# Sheet1.net
KiCad netlist of a schematic drawn in Altium Designer
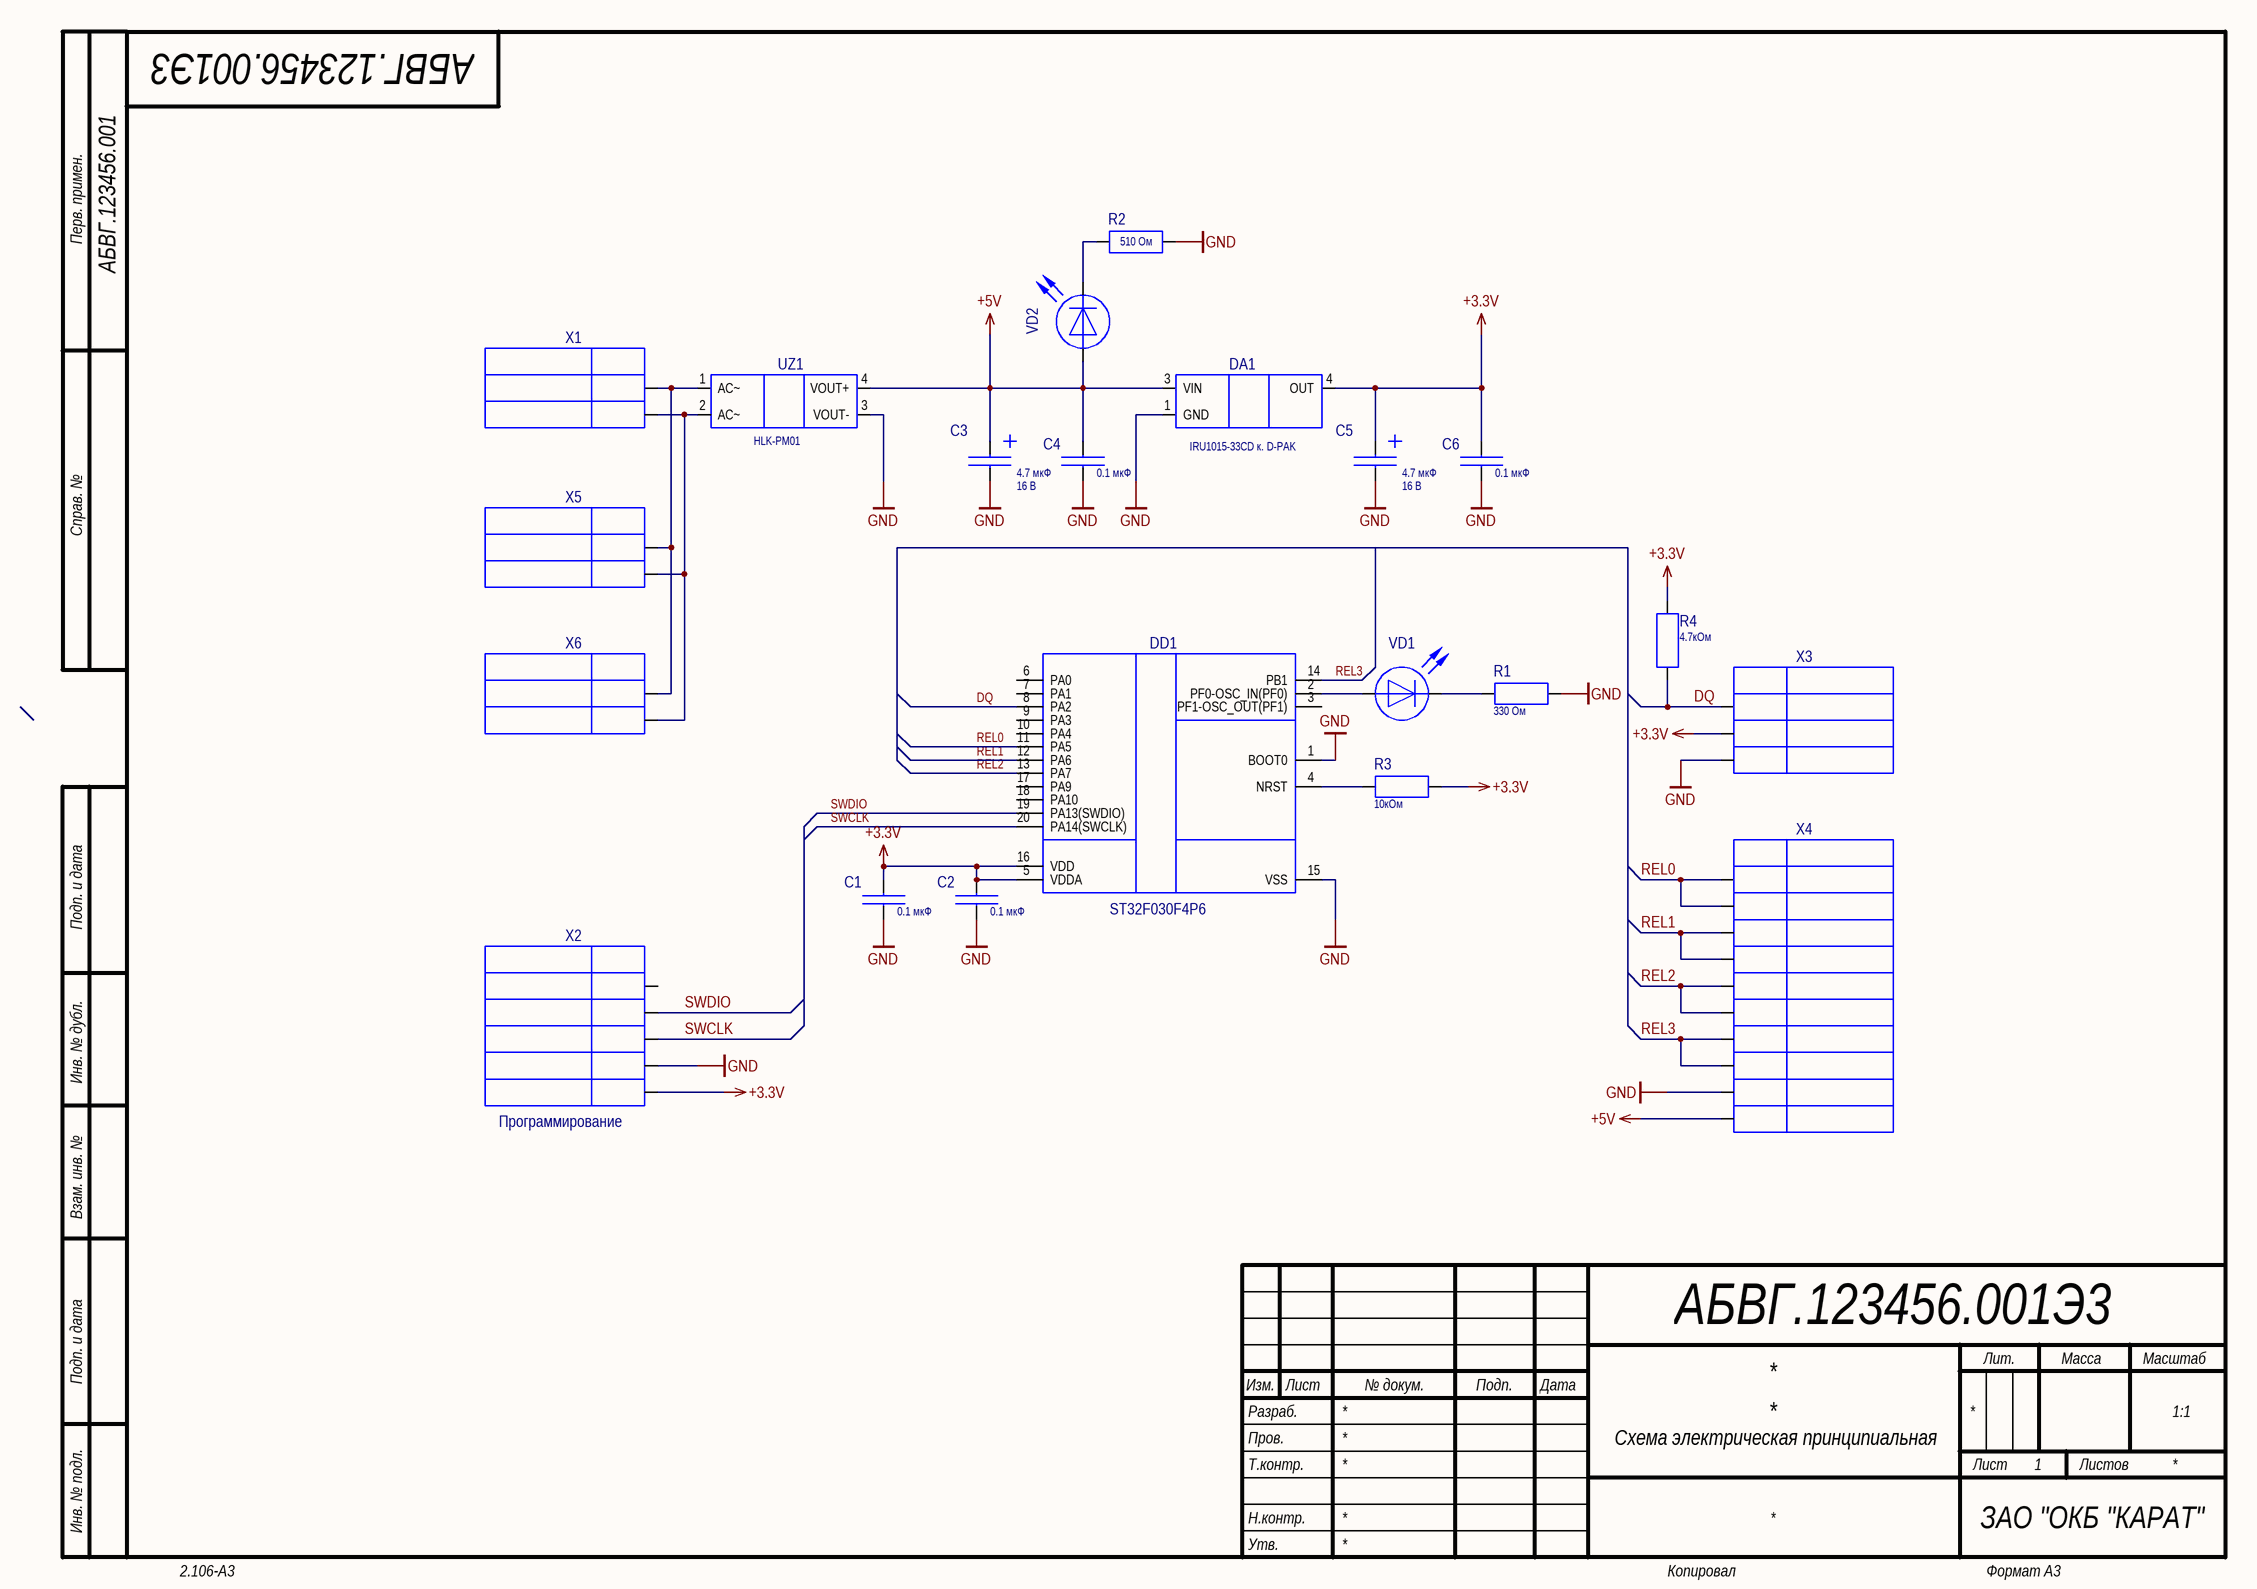
[diagram p0: Sheet1.SchDoc]

(export (version "E")
  (design (tool "Eeschema 10.0.6"))
  (components
    (comp (ref "C1")
      (value "0.1 мкФ")
      (footprint "C1206")
      (fields (field (name "TOLERANCE") "5%") (field (name "Comment") "C_2"))
      (libsource (lib "rc_lib") (part "C_2"))
    )
    (comp (ref "C2")
      (value "0.1 мкФ")
      (footprint "C1206")
      (fields (field (name "TOLERANCE") "5%") (field (name "Comment") "C_2"))
      (libsource (lib "rc_lib") (part "C_2"))
    )
    (comp (ref "C3")
      (value "4.7 мкФ")
      (footprint "B")
      (fields
        (field (name "POWER/VOLTAGE") "16 В")
        (field (name "TOLERANCE") "10%")
        (field (name "Comment") "C_E")
      )
      (libsource (lib "rc_lib") (part "C_E"))
    )
    (comp (ref "C4")
      (value "0.1 мкФ")
      (footprint "C1206")
      (fields (field (name "TOLERANCE") "5%") (field (name "Comment") "C_2"))
      (libsource (lib "rc_lib") (part "C_2"))
    )
    (comp (ref "C5")
      (value "4.7 мкФ")
      (footprint "B")
      (fields
        (field (name "POWER/VOLTAGE") "16 В")
        (field (name "TOLERANCE") "10%")
        (field (name "Comment") "C_E")
      )
      (libsource (lib "rc_lib") (part "C_E"))
    )
    (comp (ref "C6")
      (value "0.1 мкФ")
      (footprint "C1206")
      (fields (field (name "TOLERANCE") "5%") (field (name "Comment") "C_2"))
      (libsource (lib "rc_lib") (part "C_2"))
    )
    (comp (ref "DA1")
      (value "LM1117")
      (footprint "D-PAK")
      (fields
        (field (name "MANUFACTURER") "ф. IR")
        (field (name "MANUFACTURERPARTNUMBER") "IRU1015-33CD к. D-PAK")
      )
      (libsource (lib "rc_lib") (part "LM1117"))
    )
    (comp (ref "DD1")
      (value "ST32F030F4")
      (footprint "SSOP20")
      (fields (field (name "MANUFACTURER") "ф. ST") (field (name "MANUFACTURERPARTNUMBER") "ST32F030F4P6"))
      (libsource (lib "cb_lib") (part "ST32F030F4"))
    )
    (comp (ref "R1")
      (value "330 Ом")
      (footprint "R1206")
      (fields (field (name "TOLERANCE") "5%") (field (name "Comment") "R_1"))
      (libsource (lib "rc_lib") (part "R_1"))
    )
    (comp (ref "R2")
      (value "510 Ом")
      (footprint "R1206")
      (fields (field (name "TOLERANCE") "5%") (field (name "Comment") "R_1"))
      (libsource (lib "rc_lib") (part "R_1"))
    )
    (comp (ref "R3")
      (value "10кОм")
      (footprint "R1206")
      (fields (field (name "TOLERANCE") "5%") (field (name "Comment") "R_1"))
      (libsource (lib "rc_lib") (part "R_1"))
    )
    (comp (ref "R4")
      (value "4.7кОм")
      (footprint "R1206")
      (fields (field (name "TOLERANCE") "5%") (field (name "Comment") "R_1"))
      (libsource (lib "rc_lib") (part "R_1"))
    )
    (comp (ref "UZ1")
      (value "HLK-PM01")
      (footprint "HLK-PM01")
      (fields
        (field (name "MANUFACTURER") "ф. Hi-link")
        (field (name "MANUFACTURERPARTNUMBER") "HLK-PM01 5В/3Вт")
      )
      (libsource (lib "cb_lib") (part "HLK-PM01"))
    )
    (comp (ref "VD1")
      (value "LED")
      (footprint "L1206")
      (fields (field (name "MANUFACTURERPARTNUMBER") "Светодиод"))
      (libsource (lib "cb_lib") (part "LED"))
    )
    (comp (ref "VD2")
      (value "LED")
      (footprint "L1206")
      (fields
        (field (name "MANUFACTURER") "ф. Betlux Electronics")
        (field (name "MANUFACTURERPARTNUMBER") "Светодиод BL-LS0603UHR (красный)")
      )
      (libsource (lib "cb_lib") (part "LED"))
    )
    (comp (ref "X1")
      (value "PLS2")
      (footprint "DG126-5-02P-14-00AH")
      (fields (field (name "MANUFACTURERPARTNUMBER") "DG126-5.0-02P"))
      (libsource (lib "rc_lib") (part "PLS2"))
    )
    (comp (ref "X2")
      (value "PLS5")
      (footprint "HDR1X5")
      (fields (field (name "MANUFACTURER") "ф. Ningbo Zhenqin Electronic"))
      (libsource (lib "fc_lib") (part "PLS5"))
    )
    (comp (ref "X3")
      (value "PLS3")
      (footprint "HDR1X3")
      (fields (field (name "MANUFACTURER") "ф. Ningbo Zhenqin Electronic"))
      (libsource (lib "cb_lib") (part "PLS3"))
    )
    (comp (ref "X4")
      (value "BH10")
      (footprint "BH10")
      (fields
        (field (name "MANUFACTURER") "ф. Ningbo Zhenqin Electronic")
        (field (name "MANUFACTURERPARTNUMBER") "BH-10")
      )
      (libsource (lib "cb_lib") (part "BH10"))
    )
    (comp (ref "X5")
      (value "PLS2")
      (footprint "DG126-5-02P-14-00AH")
      (fields (field (name "MANUFACTURERPARTNUMBER") "DG126-5.0-02P"))
      (libsource (lib "rc_lib") (part "PLS2"))
    )
    (comp (ref "X6")
      (value "PLS2")
      (footprint "DG126-5-02P-14-00AH")
      (fields (field (name "MANUFACTURERPARTNUMBER") "DG126-5.0-02P"))
      (libsource (lib "rc_lib") (part "PLS2"))
    )
  )
  (nets
    (net (code "1") (name "+3.3V") (class "Default")
      (node (ref "C1") (pin "2") (pintype "passive"))
      (node (ref "C2") (pin "2") (pintype "passive"))
      (node (ref "C5") (pin "1") (pintype "passive"))
      (node (ref "C6") (pin "2") (pintype "passive"))
      (node (ref "DA1") (pin "4") (pinfunction "OUT_4") (pintype "passive"))
      (node (ref "DD1") (pin "16") (pinfunction "VDD_16") (pintype "passive"))
      (node (ref "DD1") (pin "5") (pinfunction "VDDA_5") (pintype "passive"))
      (node (ref "R3") (pin "2") (pintype "passive"))
      (node (ref "R4") (pin "2") (pintype "passive"))
      (node (ref "X2") (pin "5") (pintype "passive"))
      (node (ref "X3") (pin "2") (pintype "passive"))
    )
    (net (code "2") (name "+5V") (class "Default")
      (node (ref "C3") (pin "1") (pintype "passive"))
      (node (ref "C4") (pin "2") (pintype "passive"))
      (node (ref "DA1") (pin "3") (pinfunction "VIN_3") (pintype "passive"))
      (node (ref "UZ1") (pin "4") (pinfunction "VOUT+_4") (pintype "passive"))
      (node (ref "VD2") (pin "1") (pintype "passive"))
      (node (ref "X4") (pin "10") (pintype "passive"))
    )
    (net (code "3") (name "/DQ") (class "Default")
      (node (ref "DD1") (pin "8") (pinfunction "PA2_8") (pintype "passive"))
      (node (ref "R4") (pin "1") (pintype "passive"))
      (node (ref "X3") (pin "1") (pintype "passive"))
    )
    (net (code "4") (name "/REL0") (class "Default")
      (node (ref "DD1") (pin "11") (pinfunction "PA5_11") (pintype "passive"))
      (node (ref "X4") (pin "1") (pintype "passive"))
      (node (ref "X4") (pin "2") (pintype "passive"))
    )
    (net (code "5") (name "/REL1") (class "Default")
      (node (ref "DD1") (pin "12") (pinfunction "PA6_12") (pintype "passive"))
      (node (ref "X4") (pin "3") (pintype "passive"))
      (node (ref "X4") (pin "4") (pintype "passive"))
    )
    (net (code "6") (name "/REL2") (class "Default")
      (node (ref "DD1") (pin "13") (pinfunction "PA7_13") (pintype "passive"))
      (node (ref "X4") (pin "5") (pintype "passive"))
      (node (ref "X4") (pin "6") (pintype "passive"))
    )
    (net (code "7") (name "/REL3") (class "Default")
      (node (ref "DD1") (pin "14") (pinfunction "PB1_14") (pintype "passive"))
      (node (ref "X4") (pin "7") (pintype "passive"))
      (node (ref "X4") (pin "8") (pintype "passive"))
    )
    (net (code "8") (name "/SWCLK") (class "Default")
      (node (ref "DD1") (pin "20") (pinfunction "PA14(SWCLK)_20") (pintype "passive"))
      (node (ref "X2") (pin "3") (pintype "passive"))
    )
    (net (code "9") (name "/SWDIO") (class "Default")
      (node (ref "DD1") (pin "19") (pinfunction "PA13(SWDIO)_19") (pintype "passive"))
      (node (ref "X2") (pin "2") (pintype "passive"))
    )
    (net (code "10") (name "GND") (class "Default")
      (node (ref "C1") (pin "1") (pintype "passive"))
      (node (ref "C2") (pin "1") (pintype "passive"))
      (node (ref "C3") (pin "2") (pintype "passive"))
      (node (ref "C4") (pin "1") (pintype "passive"))
      (node (ref "C5") (pin "2") (pintype "passive"))
      (node (ref "C6") (pin "1") (pintype "passive"))
      (node (ref "DA1") (pin "1") (pinfunction "GND_1") (pintype "passive"))
      (node (ref "DD1") (pin "1") (pinfunction "BOOT0_1") (pintype "passive"))
      (node (ref "DD1") (pin "15") (pinfunction "VSS_15") (pintype "passive"))
      (node (ref "R1") (pin "2") (pintype "passive"))
      (node (ref "R2") (pin "1") (pintype "passive"))
      (node (ref "UZ1") (pin "3") (pinfunction "VOUT-_3") (pintype "passive"))
      (node (ref "X2") (pin "4") (pintype "passive"))
      (node (ref "X3") (pin "3") (pintype "passive"))
      (node (ref "X4") (pin "9") (pintype "passive"))
    )
    (net (code "11") (name "Net-(DD1-NRST)") (class "Default")
      (node (ref "DD1") (pin "4") (pinfunction "NRST_4") (pintype "passive"))
      (node (ref "R3") (pin "1") (pintype "passive"))
    )
    (net (code "12") (name "Net-(DD1-PF0-OSC_IN(PF0))") (class "Default")
      (node (ref "DD1") (pin "2") (pinfunction "PF0-OSC_IN(PF0)_2") (pintype "passive"))
      (node (ref "VD1") (pin "1") (pintype "passive"))
    )
    (net (code "13") (name "Net-(R1-Pad1)") (class "Default")
      (node (ref "R1") (pin "1") (pintype "passive"))
      (node (ref "VD1") (pin "2") (pintype "passive"))
    )
    (net (code "14") (name "Net-(R2-Pad2)") (class "Default")
      (node (ref "R2") (pin "2") (pintype "passive"))
      (node (ref "VD2") (pin "2") (pintype "passive"))
    )
    (net (code "15") (name "Net-(UZ1-AC~-Pad1)") (class "Default")
      (node (ref "UZ1") (pin "1") (pinfunction "AC~_1") (pintype "passive"))
      (node (ref "X1") (pin "2") (pintype "passive"))
      (node (ref "X5") (pin "2") (pintype "passive"))
      (node (ref "X6") (pin "2") (pintype "passive"))
    )
    (net (code "16") (name "Net-(UZ1-AC~-Pad2)") (class "Default")
      (node (ref "UZ1") (pin "2") (pinfunction "AC~_2") (pintype "passive"))
      (node (ref "X1") (pin "1") (pintype "passive"))
      (node (ref "X5") (pin "1") (pintype "passive"))
      (node (ref "X6") (pin "1") (pintype "passive"))
    )
    (net (code "17") (name "unconnected-(DD1-PA0-Pad6)") (class "Default")
      (node (ref "DD1") (pin "6") (pinfunction "PA0_6") (pintype "passive"))
    )
    (net (code "18") (name "unconnected-(DD1-PA1-Pad7)") (class "Default")
      (node (ref "DD1") (pin "7") (pinfunction "PA1_7") (pintype "passive"))
    )
    (net (code "19") (name "unconnected-(DD1-PA3-Pad9)") (class "Default")
      (node (ref "DD1") (pin "9") (pinfunction "PA3_9") (pintype "passive"))
    )
    (net (code "20") (name "unconnected-(DD1-PA4-Pad10)") (class "Default")
      (node (ref "DD1") (pin "10") (pinfunction "PA4_10") (pintype "passive"))
    )
    (net (code "21") (name "unconnected-(DD1-PA9-Pad17)") (class "Default")
      (node (ref "DD1") (pin "17") (pinfunction "PA9_17") (pintype "passive"))
    )
    (net (code "22") (name "unconnected-(DD1-PA10-Pad18)") (class "Default")
      (node (ref "DD1") (pin "18") (pinfunction "PA10_18") (pintype "passive"))
    )
    (net (code "23") (name "unconnected-(DD1-PF1-OSC_OUT(PF1)-Pad3)") (class "Default")
      (node (ref "DD1") (pin "3") (pinfunction "PF1-OSC_OUT(PF1)_3") (pintype "passive"))
    )
    (net (code "24") (name "unconnected-(X2-Pad1)") (class "Default")
      (node (ref "X2") (pin "1") (pintype "passive"))
    )
  )
)
